# RFM69W-V1_0.net
KiCad netlist of a schematic drawn in EAGLE
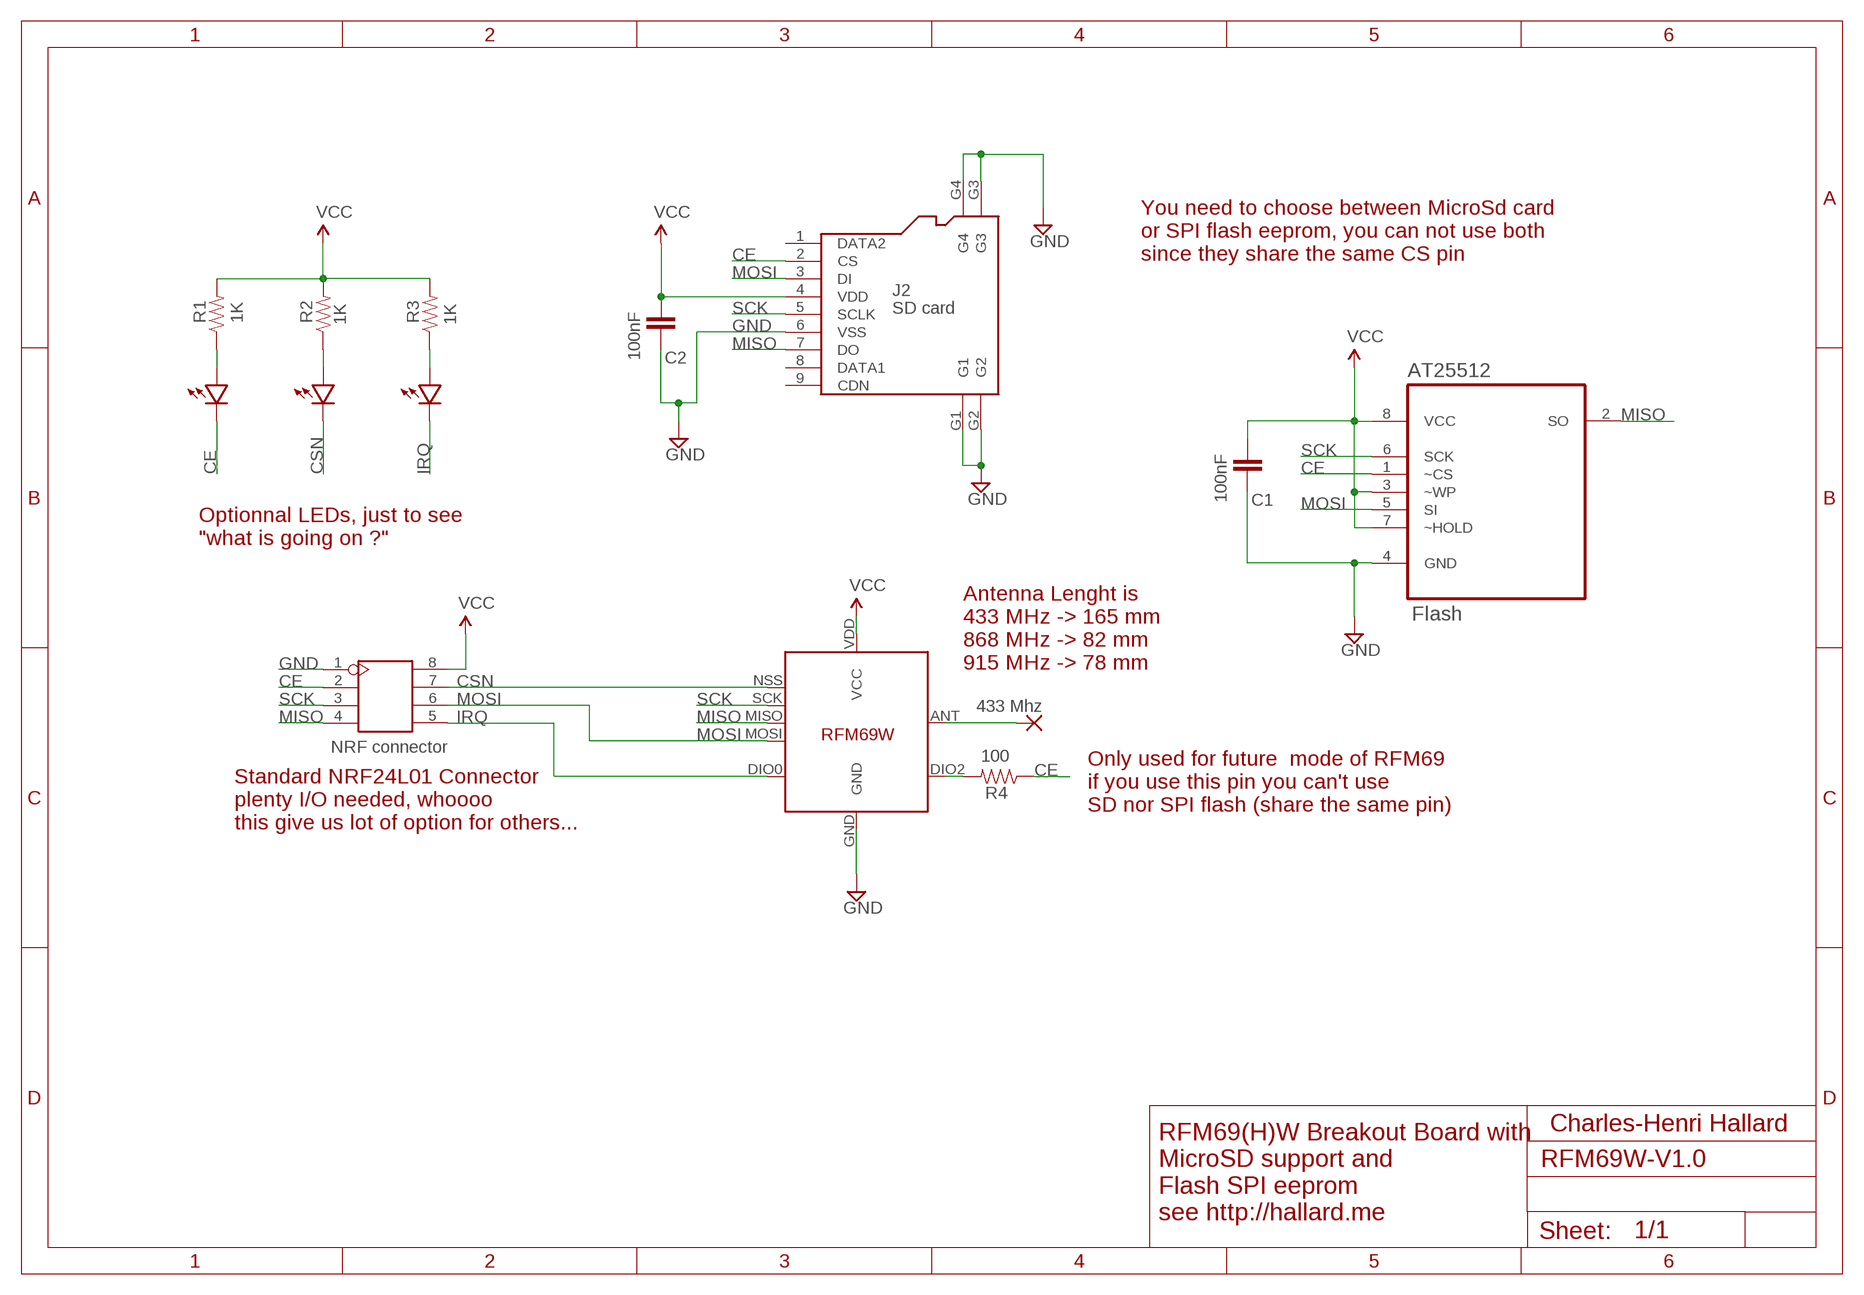
[diagram p0: schematic, sheet 1]

(export (version "E")
  (design (tool "Eeschema 10.0.6"))
  (components
    (comp (ref "ANT.")
      (value "433 Mhz")
      (footprint "eagle-import:1,6_0,8")
      (libsource (lib "eagle-import") (part "1,6/0,8"))
    )
    (comp (ref "AT25512")
      (value "Flash")
      (footprint "eagle-import:SOIC127P600X175-8N")
      (fields (field (name "MPN") "AT25512N-SH-B"))
      (libsource (lib "eagle-import") (part "AT25512N-SH-B"))
    )
    (comp (ref "C1")
      (value "100nF")
      (footprint "eagle-import:0805-CAP")
      (libsource (lib "eagle-import") (part "CAP0805-CAP"))
    )
    (comp (ref "C2")
      (value "100nF")
      (footprint "eagle-import:0805-CAP")
      (libsource (lib "eagle-import") (part "CAP0805-CAP"))
    )
    (comp (ref "J1")
      (value "NRF connector")
      (footprint "eagle-import:2X4P-2.54")
      (libsource (lib "eagle-import") (part "HEADER-2X4P-2.54"))
    )
    (comp (ref "J2")
      (value "SD card")
      (footprint "eagle-import:9P-SMD-W_-RING")
      (libsource (lib "eagle-import") (part "HOLDER-MICROSD-9P"))
    )
    (comp (ref "R1")
      (value "1K")
      (footprint "eagle-import:0805-RES")
      (libsource (lib "eagle-import") (part "RESISTOR0805-RES"))
    )
    (comp (ref "R2")
      (value "1K")
      (footprint "eagle-import:0805-RES")
      (libsource (lib "eagle-import") (part "RESISTOR0805-RES"))
    )
    (comp (ref "R3")
      (value "1K")
      (footprint "eagle-import:0805-RES")
      (libsource (lib "eagle-import") (part "RESISTOR0805-RES"))
    )
    (comp (ref "R4")
      (value "100")
      (footprint "eagle-import:0805-RES")
      (libsource (lib "eagle-import") (part "RESISTOR0805-RES"))
    )
    (comp (ref "U$1")
      (value "RFM69")
      (footprint "eagle-import:RFM69W-MINPADS")
      (libsource (lib "eagle-import") (part "RFM69"))
    )
    (comp (ref "U$2")
      (value "LED0805-LARGE")
      (footprint "eagle-import:0805-LED-LARGEPADS")
      (libsource (lib "eagle-import") (part "LED0805-LARGE"))
    )
    (comp (ref "U$3")
      (value "LED0805-LARGE")
      (footprint "eagle-import:0805-LED-LARGEPADS")
      (libsource (lib "eagle-import") (part "LED0805-LARGE"))
    )
    (comp (ref "U$4")
      (value "LED0805-LARGE")
      (footprint "eagle-import:0805-LED-LARGEPADS")
      (libsource (lib "eagle-import") (part "LED0805-LARGE"))
    )
  )
  (nets
    (net (code "1") (name "/CE") (class "Default")
      (node (ref "AT25512") (pin "1") (pinfunction "~{CS}_1") (pintype "input"))
      (node (ref "J1") (pin "2") (pinfunction "2_2") (pintype "bidirectional"))
      (node (ref "J2") (pin "2") (pinfunction "CS_2") (pintype "bidirectional"))
      (node (ref "R4") (pin "1") (pinfunction "1_1") (pintype "passive"))
      (node (ref "U$2") (pin "MINUS") (pinfunction "MINUS_MINUS") (pintype "passive"))
    )
    (net (code "2") (name "/CSN") (class "Default")
      (node (ref "J1") (pin "7") (pinfunction "7_7") (pintype "bidirectional"))
      (node (ref "U$1") (pin "NSS") (pinfunction "SEL_NSS") (pintype "input"))
      (node (ref "U$3") (pin "MINUS") (pinfunction "MINUS_MINUS") (pintype "passive"))
    )
    (net (code "3") (name "/IRQ") (class "Default")
      (node (ref "J1") (pin "5") (pinfunction "5_5") (pintype "bidirectional"))
      (node (ref "U$1") (pin "DIO0") (pinfunction "DIO0_DIO0") (pintype "open_collector"))
      (node (ref "U$4") (pin "MINUS") (pinfunction "MINUS_MINUS") (pintype "passive"))
    )
    (net (code "4") (name "/MISO") (class "Default")
      (node (ref "AT25512") (pin "2") (pinfunction "SO_2") (pintype "output"))
      (node (ref "J1") (pin "4") (pinfunction "4_4") (pintype "bidirectional"))
      (node (ref "J2") (pin "7") (pinfunction "DO_7") (pintype "bidirectional"))
      (node (ref "U$1") (pin "MISO") (pinfunction "MISO_MISO") (pintype "input"))
    )
    (net (code "5") (name "/MOSI") (class "Default")
      (node (ref "AT25512") (pin "5") (pinfunction "SI_5") (pintype "input"))
      (node (ref "J1") (pin "6") (pinfunction "6_6") (pintype "bidirectional"))
      (node (ref "J2") (pin "3") (pinfunction "DI_3") (pintype "bidirectional"))
      (node (ref "U$1") (pin "MOSI") (pinfunction "MOSI_MOSI") (pintype "output"))
    )
    (net (code "6") (name "/SCK") (class "Default")
      (node (ref "AT25512") (pin "6") (pinfunction "SCK_6") (pintype "input"))
      (node (ref "J1") (pin "3") (pinfunction "3_3") (pintype "bidirectional"))
      (node (ref "J2") (pin "5") (pinfunction "SCLK_5") (pintype "bidirectional"))
      (node (ref "U$1") (pin "SCK") (pinfunction "SCK_SCK") (pintype "input"))
    )
    (net (code "7") (name "GND") (class "Default")
      (node (ref "AT25512") (pin "4") (pinfunction "GND_4") (pintype "passive"))
      (node (ref "C1") (pin "2") (pinfunction "2_2") (pintype "passive"))
      (node (ref "C2") (pin "2") (pinfunction "2_2") (pintype "passive"))
      (node (ref "J1") (pin "1") (pinfunction "1_1") (pintype "bidirectional"))
      (node (ref "J2") (pin "6") (pinfunction "VSS_6") (pintype "bidirectional"))
      (node (ref "J2") (pin "G1") (pinfunction "G1_G1") (pintype "bidirectional"))
      (node (ref "J2") (pin "G2") (pinfunction "G2_G2") (pintype "bidirectional"))
      (node (ref "J2") (pin "G3") (pinfunction "G3_G3") (pintype "bidirectional"))
      (node (ref "J2") (pin "G4") (pinfunction "G4_G4") (pintype "bidirectional"))
      (node (ref "U$1") (pin "GND") (pinfunction "GND_GND") (pintype "power_in"))
    )
    (net (code "8") (name "Net-(ANT.-P)") (class "Default")
      (node (ref "ANT.") (pin "1") (pinfunction "P_1") (pintype "passive"))
      (node (ref "U$1") (pin "ANT") (pinfunction "ANT_ANT") (pintype "passive"))
    )
    (net (code "9") (name "Net-(R1-Pad1)") (class "Default")
      (node (ref "R1") (pin "1") (pinfunction "1_1") (pintype "passive"))
      (node (ref "U$2") (pin "PLUS") (pinfunction "PLUS_PLUS") (pintype "passive"))
    )
    (net (code "10") (name "Net-(R2-Pad1)") (class "Default")
      (node (ref "R2") (pin "1") (pinfunction "1_1") (pintype "passive"))
      (node (ref "U$3") (pin "PLUS") (pinfunction "PLUS_PLUS") (pintype "passive"))
    )
    (net (code "11") (name "Net-(R3-Pad1)") (class "Default")
      (node (ref "R3") (pin "1") (pinfunction "1_1") (pintype "passive"))
      (node (ref "U$4") (pin "PLUS") (pinfunction "PLUS_PLUS") (pintype "passive"))
    )
    (net (code "12") (name "Net-(R4-Pad2)") (class "Default")
      (node (ref "R4") (pin "2") (pinfunction "2_2") (pintype "passive"))
      (node (ref "U$1") (pin "DIO2") (pinfunction "DIO2_DIO2") (pintype "open_collector"))
    )
    (net (code "13") (name "VCC") (class "Default")
      (node (ref "AT25512") (pin "3") (pinfunction "~{WP}_3") (pintype "input"))
      (node (ref "AT25512") (pin "7") (pinfunction "~{HOLD}_7") (pintype "input"))
      (node (ref "AT25512") (pin "8") (pinfunction "VCC_8") (pintype "power_in"))
      (node (ref "C1") (pin "1") (pinfunction "1_1") (pintype "passive"))
      (node (ref "C2") (pin "1") (pinfunction "1_1") (pintype "passive"))
      (node (ref "J1") (pin "8") (pinfunction "8_8") (pintype "bidirectional"))
      (node (ref "J2") (pin "4") (pinfunction "VDD_4") (pintype "bidirectional"))
      (node (ref "R1") (pin "2") (pinfunction "2_2") (pintype "passive"))
      (node (ref "R2") (pin "2") (pinfunction "2_2") (pintype "passive"))
      (node (ref "R3") (pin "2") (pinfunction "2_2") (pintype "passive"))
      (node (ref "U$1") (pin "VDD") (pinfunction "VCC_VDD") (pintype "power_in"))
    )
    (net (code "14") (name "unconnected-(J2-CDN-Pad9)") (class "Default")
      (node (ref "J2") (pin "9") (pinfunction "CDN_9") (pintype "bidirectional"))
    )
    (net (code "15") (name "unconnected-(J2-DATA1-Pad8)") (class "Default")
      (node (ref "J2") (pin "8") (pinfunction "DATA1_8") (pintype "bidirectional"))
    )
    (net (code "16") (name "unconnected-(J2-DATA2-Pad1)") (class "Default")
      (node (ref "J2") (pin "1") (pinfunction "DATA2_1") (pintype "bidirectional"))
    )
  )
)
